# temperature.net
KiCad netlist of a schematic drawn in Altium Designer
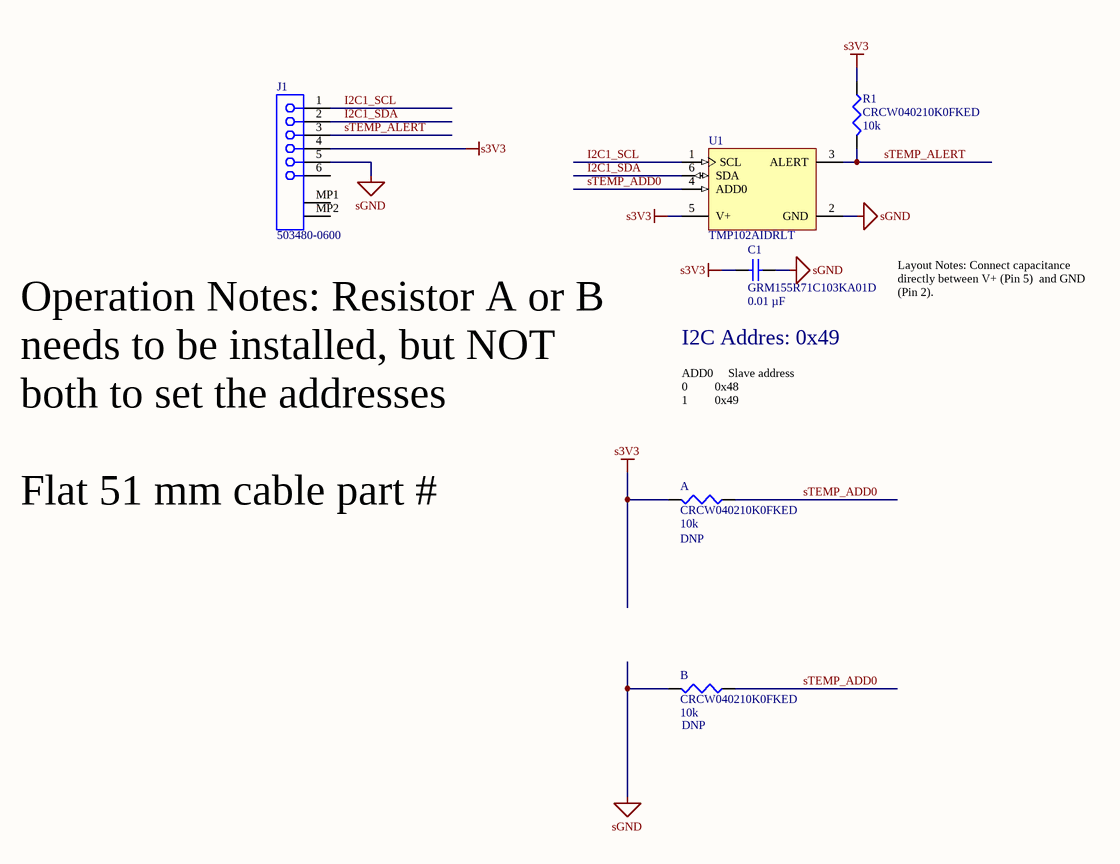
[diagram p0: temperature.SchDoc]

(export (version "E")
  (design (tool "Eeschema 10.0.6"))
  (components
    (comp (ref "A")
      (value "CRCW040210K0FKED")
      (footprint "0402")
      (description "0.125W, -55-155C, 1005, 50V, ±1%")
      (fields (field (name "ALTIUM_UNNAMED_1") "DNP") (field (name "ALTIUM_VALUE") "10k"))
      (libsource (lib "standard_resistors") (part "CRCW0402xxxxFKED"))
    )
    (comp (ref "B")
      (value "CRCW040210K0FKED")
      (footprint "0402")
      (description "0.125W, -55-155C, 1005, 50V, ±1%")
      (fields (field (name "ALTIUM_UNNAMED_1") "DNP") (field (name "ALTIUM_VALUE") "10k"))
      (libsource (lib "standard_resistors") (part "CRCW0402xxxxFKED"))
    )
    (comp (ref "C1")
      (value "GRM155R71C103KA01D")
      (footprint "0402")
      (description "Cap, 0.01 µF, 16 V, X7R")
      (fields (field (name "ALTIUM_VALUE") "0.01 µF") (field (name "PUBLISHER") "Altium Limited"))
      (libsource (lib "miscellaneous_devices") (part "Cap"))
    )
    (comp (ref "J1")
      (value "503480-0600")
      (footprint "MOLX-503480-0600")
      (fields (field (name "MANUFACTURER") "Molex"))
      (libsource (lib "Altium Content Vault") (part "MOLX-503480-0600"))
    )
    (comp (ref "R1")
      (value "CRCW040210K0FKED")
      (footprint "0402")
      (description "0.125W, -55-155C, 1005, 50V, ±1%")
      (fields (field (name "ALTIUM_VALUE") "10k"))
      (libsource (lib "standard_resistors") (part "CRCW0402xxxxFKED"))
    )
    (comp (ref "U1")
      (value "TMP102AIDRLT")
      (footprint "DRL0006A_L")
      (libsource (lib "Altium Content Vault") (part "TI-TMP102AIDRLT-DRL6"))
    )
  )
  (nets
    (net (code "1") (name "/I2C1_SCL") (class "Default")
      (node (ref "J1") (pin "1") (pinfunction "1_1") (pintype "passive"))
      (node (ref "U1") (pin "1") (pinfunction "SCL_1") (pintype "input"))
    )
    (net (code "2") (name "/I2C1_SDA") (class "Default")
      (node (ref "J1") (pin "2") (pinfunction "2_2") (pintype "passive"))
      (node (ref "U1") (pin "6") (pinfunction "SDA_6") (pintype "bidirectional"))
    )
    (net (code "3") (name "/sTEMP_ADD0") (class "Default")
      (node (ref "A") (pin "1") (pinfunction "1_1") (pintype "passive"))
      (node (ref "B") (pin "1") (pinfunction "1_1") (pintype "passive"))
      (node (ref "U1") (pin "4") (pinfunction "ADD0_4") (pintype "input"))
    )
    (net (code "4") (name "/sTEMP_ALERT") (class "Default")
      (node (ref "J1") (pin "3") (pinfunction "3_3") (pintype "passive"))
      (node (ref "R1") (pin "2") (pinfunction "2_2") (pintype "passive"))
      (node (ref "U1") (pin "3") (pinfunction "ALERT_3") (pintype "open_collector"))
    )
    (net (code "5") (name "s3V3") (class "Default")
      (node (ref "A") (pin "2") (pinfunction "2_2") (pintype "passive"))
      (node (ref "C1") (pin "2") (pinfunction "2_2") (pintype "passive"))
      (node (ref "J1") (pin "4") (pinfunction "4_4") (pintype "passive"))
      (node (ref "R1") (pin "1") (pinfunction "1_1") (pintype "passive"))
      (node (ref "U1") (pin "5") (pinfunction "V+_5") (pintype "power_in"))
    )
    (net (code "6") (name "sGND") (class "Default")
      (node (ref "B") (pin "2") (pinfunction "2_2") (pintype "passive"))
      (node (ref "C1") (pin "1") (pinfunction "1_1") (pintype "passive"))
      (node (ref "J1") (pin "5") (pinfunction "5_5") (pintype "passive"))
      (node (ref "U1") (pin "2") (pinfunction "GND_2") (pintype "power_in"))
    )
    (net (code "7") (name "unconnected-(J1-Pad6)") (class "Default")
      (node (ref "J1") (pin "6") (pinfunction "6_6") (pintype "passive"))
    )
    (net (code "8") (name "unconnected-(J1-PadMP1)") (class "Default")
      (node (ref "J1") (pin "MP1") (pinfunction "MP1_MP1") (pintype "passive"))
    )
    (net (code "9") (name "unconnected-(J1-PadMP2)") (class "Default")
      (node (ref "J1") (pin "MP2") (pinfunction "MP2_MP2") (pintype "passive"))
    )
  )
)
